# breakout.net
KiCad netlist of a schematic drawn in EAGLE
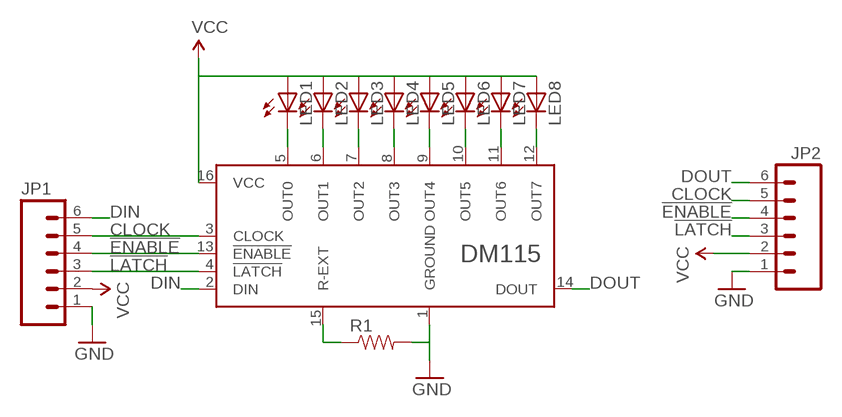
[diagram p0: schematic, sheet 1]

(export (version "E")
  (design (tool "Eeschema 10.0.6"))
  (components
    (comp (ref "JP1")
      (value "M06SIP")
      (footprint "eagle-import:1X06")
      (libsource (lib "eagle-import") (part "M06SIP"))
    )
    (comp (ref "JP2")
      (value "M06SIP")
      (footprint "eagle-import:1X06")
      (libsource (lib "eagle-import") (part "M06SIP"))
    )
    (comp (ref "LED1")
      (value "LEDOVAL")
      (footprint "eagle-import:LED-OVAL")
      (libsource (lib "eagle-import") (part "LEDOVAL"))
    )
    (comp (ref "LED2")
      (value "LEDOVAL")
      (footprint "eagle-import:LED-OVAL")
      (libsource (lib "eagle-import") (part "LEDOVAL"))
    )
    (comp (ref "LED3")
      (value "LEDOVAL")
      (footprint "eagle-import:LED-OVAL")
      (libsource (lib "eagle-import") (part "LEDOVAL"))
    )
    (comp (ref "LED4")
      (value "LEDOVAL")
      (footprint "eagle-import:LED-OVAL")
      (libsource (lib "eagle-import") (part "LEDOVAL"))
    )
    (comp (ref "LED5")
      (value "LEDOVAL")
      (footprint "eagle-import:LED-OVAL")
      (libsource (lib "eagle-import") (part "LEDOVAL"))
    )
    (comp (ref "LED6")
      (value "LEDOVAL")
      (footprint "eagle-import:LED-OVAL")
      (libsource (lib "eagle-import") (part "LEDOVAL"))
    )
    (comp (ref "LED7")
      (value "LEDOVAL")
      (footprint "eagle-import:LED-OVAL")
      (libsource (lib "eagle-import") (part "LEDOVAL"))
    )
    (comp (ref "LED8")
      (value "LEDOVAL")
      (footprint "eagle-import:LED-OVAL")
      (libsource (lib "eagle-import") (part "LEDOVAL"))
    )
    (comp (ref "R1")
      (value "RESISTORAXIAL-0.3")
      (footprint "eagle-import:AXIAL-0.3")
      (libsource (lib "eagle-import") (part "RESISTORAXIAL-0.3"))
    )
    (comp (ref "U$1")
      (value "DM115DIP16")
      (footprint "eagle-import:DIL16")
      (libsource (lib "eagle-import") (part "DM115DIP16"))
    )
  )
  (nets
    (net (code "1") (name "/CLOCK") (class "Default")
      (node (ref "JP1") (pin "5") (pinfunction "5_5") (pintype "passive"))
      (node (ref "JP2") (pin "5") (pinfunction "5_5") (pintype "passive"))
      (node (ref "U$1") (pin "3") (pinfunction "CLOCK_3") (pintype "bidirectional"))
    )
    (net (code "2") (name "/DIN") (class "Default")
      (node (ref "JP1") (pin "6") (pinfunction "6_6") (pintype "passive"))
      (node (ref "U$1") (pin "2") (pinfunction "DIN_2") (pintype "bidirectional"))
    )
    (net (code "3") (name "/DOUT") (class "Default")
      (node (ref "JP2") (pin "6") (pinfunction "6_6") (pintype "passive"))
      (node (ref "U$1") (pin "14") (pinfunction "DOUT_14") (pintype "bidirectional"))
    )
    (net (code "4") (name "/~{ENABLE}") (class "Default")
      (node (ref "JP1") (pin "4") (pinfunction "4_4") (pintype "passive"))
      (node (ref "JP2") (pin "4") (pinfunction "4_4") (pintype "passive"))
      (node (ref "U$1") (pin "13") (pinfunction "~{ENABLE}_13") (pintype "bidirectional"))
    )
    (net (code "5") (name "/~{LATCH}") (class "Default")
      (node (ref "JP1") (pin "3") (pinfunction "3_3") (pintype "passive"))
      (node (ref "JP2") (pin "3") (pinfunction "3_3") (pintype "passive"))
      (node (ref "U$1") (pin "4") (pinfunction "~{LATCH}_4") (pintype "bidirectional"))
    )
    (net (code "6") (name "GND") (class "Default")
      (node (ref "JP1") (pin "1") (pinfunction "1_1") (pintype "passive"))
      (node (ref "JP2") (pin "1") (pinfunction "1_1") (pintype "passive"))
      (node (ref "R1") (pin "P$2") (pinfunction "2_P$2") (pintype "passive"))
      (node (ref "U$1") (pin "1") (pinfunction "GROUND_1") (pintype "bidirectional"))
    )
    (net (code "7") (name "Net-(LED1-C)") (class "Default")
      (node (ref "LED1") (pin "CATHODE") (pinfunction "C_CATHODE") (pintype "passive"))
      (node (ref "U$1") (pin "5") (pinfunction "OUT0_5") (pintype "bidirectional"))
    )
    (net (code "8") (name "Net-(LED2-C)") (class "Default")
      (node (ref "LED2") (pin "CATHODE") (pinfunction "C_CATHODE") (pintype "passive"))
      (node (ref "U$1") (pin "6") (pinfunction "OUT1_6") (pintype "bidirectional"))
    )
    (net (code "9") (name "Net-(LED3-C)") (class "Default")
      (node (ref "LED3") (pin "CATHODE") (pinfunction "C_CATHODE") (pintype "passive"))
      (node (ref "U$1") (pin "7") (pinfunction "OUT2_7") (pintype "bidirectional"))
    )
    (net (code "10") (name "Net-(LED4-C)") (class "Default")
      (node (ref "LED4") (pin "CATHODE") (pinfunction "C_CATHODE") (pintype "passive"))
      (node (ref "U$1") (pin "8") (pinfunction "OUT3_8") (pintype "bidirectional"))
    )
    (net (code "11") (name "Net-(LED5-C)") (class "Default")
      (node (ref "LED5") (pin "CATHODE") (pinfunction "C_CATHODE") (pintype "passive"))
      (node (ref "U$1") (pin "9") (pinfunction "OUT4_9") (pintype "bidirectional"))
    )
    (net (code "12") (name "Net-(LED6-C)") (class "Default")
      (node (ref "LED6") (pin "CATHODE") (pinfunction "C_CATHODE") (pintype "passive"))
      (node (ref "U$1") (pin "10") (pinfunction "OUT5_10") (pintype "bidirectional"))
    )
    (net (code "13") (name "Net-(LED7-C)") (class "Default")
      (node (ref "LED7") (pin "CATHODE") (pinfunction "C_CATHODE") (pintype "passive"))
      (node (ref "U$1") (pin "11") (pinfunction "OUT6_11") (pintype "bidirectional"))
    )
    (net (code "14") (name "Net-(LED8-C)") (class "Default")
      (node (ref "LED8") (pin "CATHODE") (pinfunction "C_CATHODE") (pintype "passive"))
      (node (ref "U$1") (pin "12") (pinfunction "OUT7_12") (pintype "bidirectional"))
    )
    (net (code "15") (name "Net-(R1-1)") (class "Default")
      (node (ref "R1") (pin "P$1") (pinfunction "1_P$1") (pintype "passive"))
      (node (ref "U$1") (pin "15") (pinfunction "R-EXT_15") (pintype "bidirectional"))
    )
    (net (code "16") (name "VCC") (class "Default")
      (node (ref "JP1") (pin "2") (pinfunction "2_2") (pintype "passive"))
      (node (ref "JP2") (pin "2") (pinfunction "2_2") (pintype "passive"))
      (node (ref "LED1") (pin "ANODE") (pinfunction "A_ANODE") (pintype "passive"))
      (node (ref "LED2") (pin "ANODE") (pinfunction "A_ANODE") (pintype "passive"))
      (node (ref "LED3") (pin "ANODE") (pinfunction "A_ANODE") (pintype "passive"))
      (node (ref "LED4") (pin "ANODE") (pinfunction "A_ANODE") (pintype "passive"))
      (node (ref "LED5") (pin "ANODE") (pinfunction "A_ANODE") (pintype "passive"))
      (node (ref "LED6") (pin "ANODE") (pinfunction "A_ANODE") (pintype "passive"))
      (node (ref "LED7") (pin "ANODE") (pinfunction "A_ANODE") (pintype "passive"))
      (node (ref "LED8") (pin "ANODE") (pinfunction "A_ANODE") (pintype "passive"))
      (node (ref "U$1") (pin "16") (pinfunction "VCC_16") (pintype "bidirectional"))
    )
  )
)
